# SCH_Hacker-Card_2024-03-19.net
KiCad netlist of a schematic drawn in EasyEDA
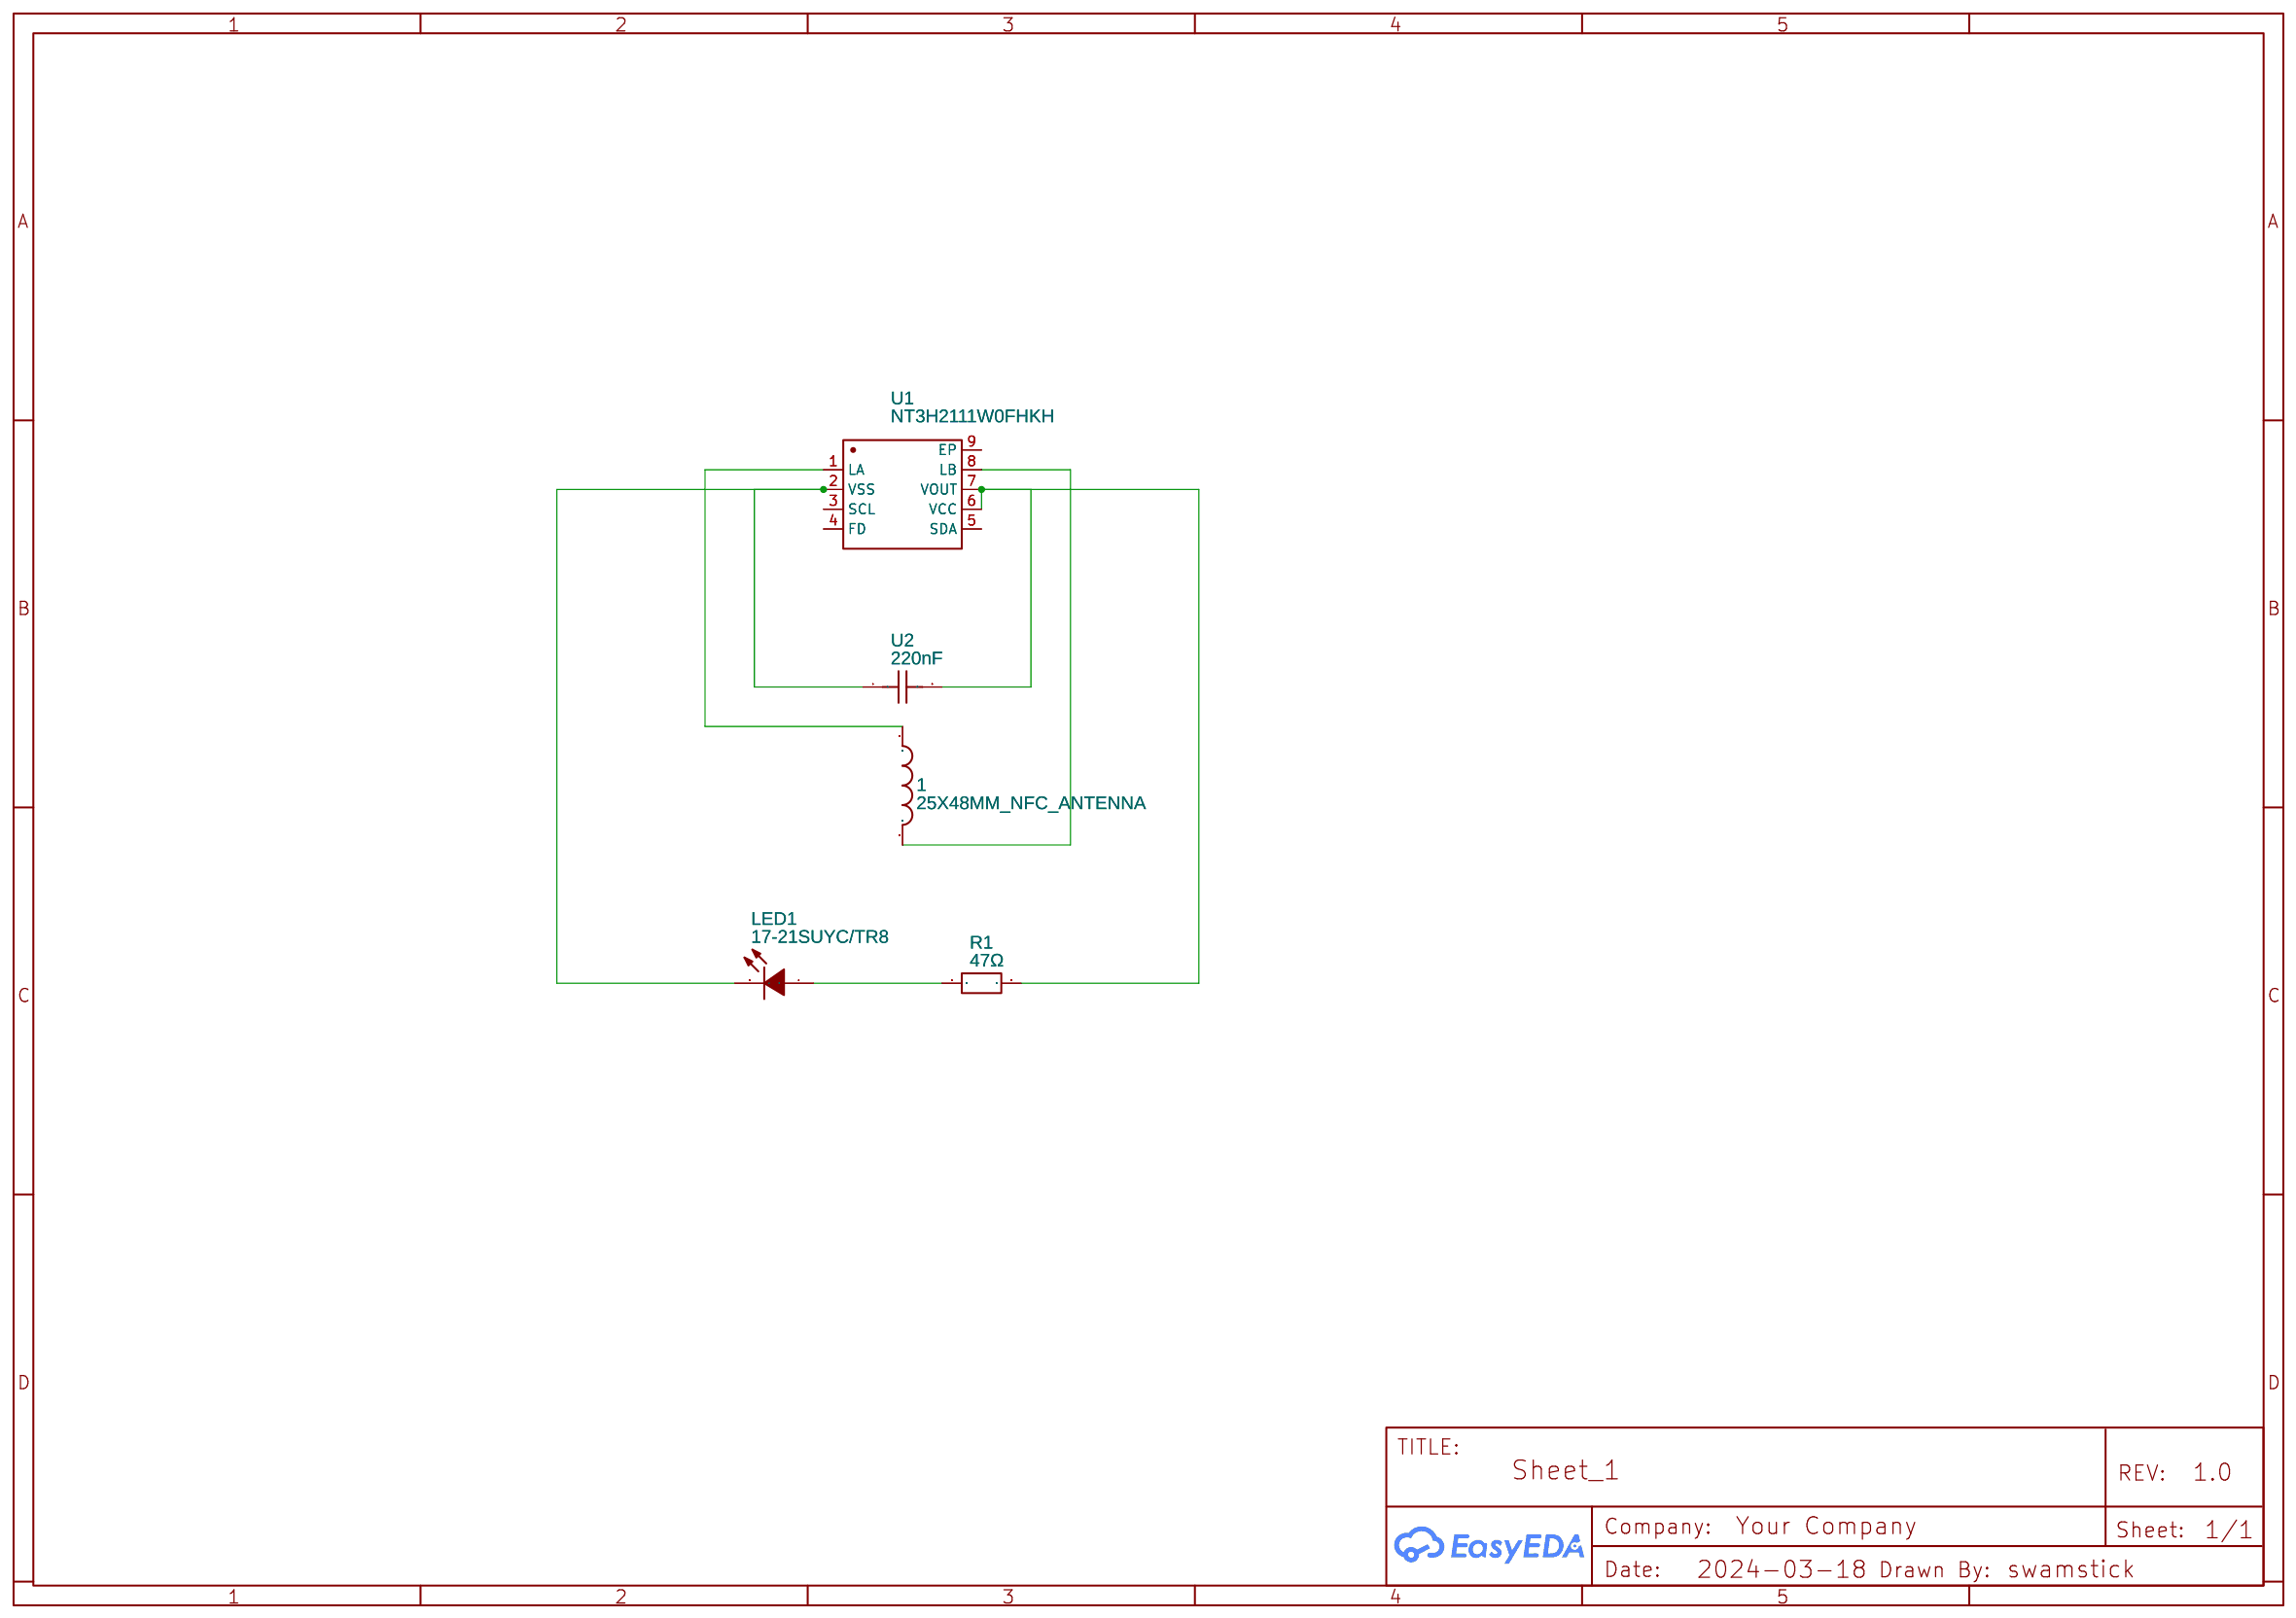
[diagram p0: schematic sheet]

(export (version "E")
  (design (tool "Eeschema 10.0.6"))
  (components
    (comp (ref "1") (value "25X48MM_NFC_ANTENNA") (libsource (lib "") (part "25X48MM_NFC_ANTENNA")))
    (comp (ref "LED1")
      (value "17-21SUYC/TR8")
      (fields (field (name "Manufacturer Part") "KT-0805黄灯") (field (name "Manufacturer") "KENTO"))
      (libsource (lib "") (part "17-21SUYC/TR8"))
    )
    (comp (ref "R1")
      (value "47Ω")
      (fields
        (field (name "Manufacturer Part") "CRCW120647R0FKEA")
        (field (name "Manufacturer") "VISHAY(威世)")
      )
      (libsource (lib "") (part "CRCW120647R0FKEA"))
    )
    (comp (ref "U1")
      (value "NT3H2111W0FHKH")
      (fields (field (name "Manufacturer") "NXP(恩智浦)"))
      (libsource (lib "") (part "NT3H2111W0FHKH"))
    )
    (comp (ref "U2")
      (value "220nF")
      (fields
        (field (name "Manufacturer Part") "UMK105BJ224KV-F")
        (field (name "Manufacturer") "TAIYO YUDEN(太诱)")
      )
      (libsource (lib "") (part "UMK105BJ224KV-F"))
    )
  )
  (nets
    (net (code "1") (name "Net-(LED1-+)") (class "Default")
      (node (ref "LED1") (pin "1") (pinfunction "+_1") (pintype "unspecified"))
      (node (ref "R1") (pin "1") (pinfunction "1_1") (pintype "unspecified"))
    )
    (net (code "2") (name "Net-(LED1--)") (class "Default")
      (node (ref "LED1") (pin "2") (pinfunction "-_2") (pintype "unspecified"))
      (node (ref "U1") (pin "2") (pinfunction "VSS_2") (pintype "unspecified"))
      (node (ref "U2") (pin "1") (pinfunction "1_1") (pintype "unspecified"))
    )
    (net (code "3") (name "Net-(U1-LA)") (class "Default")
      (node (ref "1") (pin "P$1") (pinfunction "P$1_P$1") (pintype "bidirectional"))
      (node (ref "U1") (pin "1") (pinfunction "LA_1") (pintype "unspecified"))
    )
    (net (code "4") (name "Net-(U1-LB)") (class "Default")
      (node (ref "1") (pin "P$2") (pinfunction "P$2_P$2") (pintype "bidirectional"))
      (node (ref "U1") (pin "8") (pinfunction "LB_8") (pintype "unspecified"))
    )
    (net (code "5") (name "Net-(U1-VCC)") (class "Default")
      (node (ref "R1") (pin "2") (pinfunction "2_2") (pintype "unspecified"))
      (node (ref "U1") (pin "6") (pinfunction "VCC_6") (pintype "unspecified"))
      (node (ref "U1") (pin "7") (pinfunction "VOUT_7") (pintype "unspecified"))
      (node (ref "U2") (pin "2") (pinfunction "2_2") (pintype "unspecified"))
    )
    (net (code "6") (name "unconnected-(U1-EP-Pad9)") (class "Default")
      (node (ref "U1") (pin "9") (pinfunction "EP_9") (pintype "unspecified"))
    )
    (net (code "7") (name "unconnected-(U1-FD-Pad4)") (class "Default")
      (node (ref "U1") (pin "4") (pinfunction "FD_4") (pintype "unspecified"))
    )
    (net (code "8") (name "unconnected-(U1-SCL-Pad3)") (class "Default")
      (node (ref "U1") (pin "3") (pinfunction "SCL_3") (pintype "unspecified"))
    )
    (net (code "9") (name "unconnected-(U1-SDA-Pad5)") (class "Default")
      (node (ref "U1") (pin "5") (pinfunction "SDA_5") (pintype "unspecified"))
    )
  )
)
